# POWER.net
KiCad netlist of a schematic drawn in Altium Designer
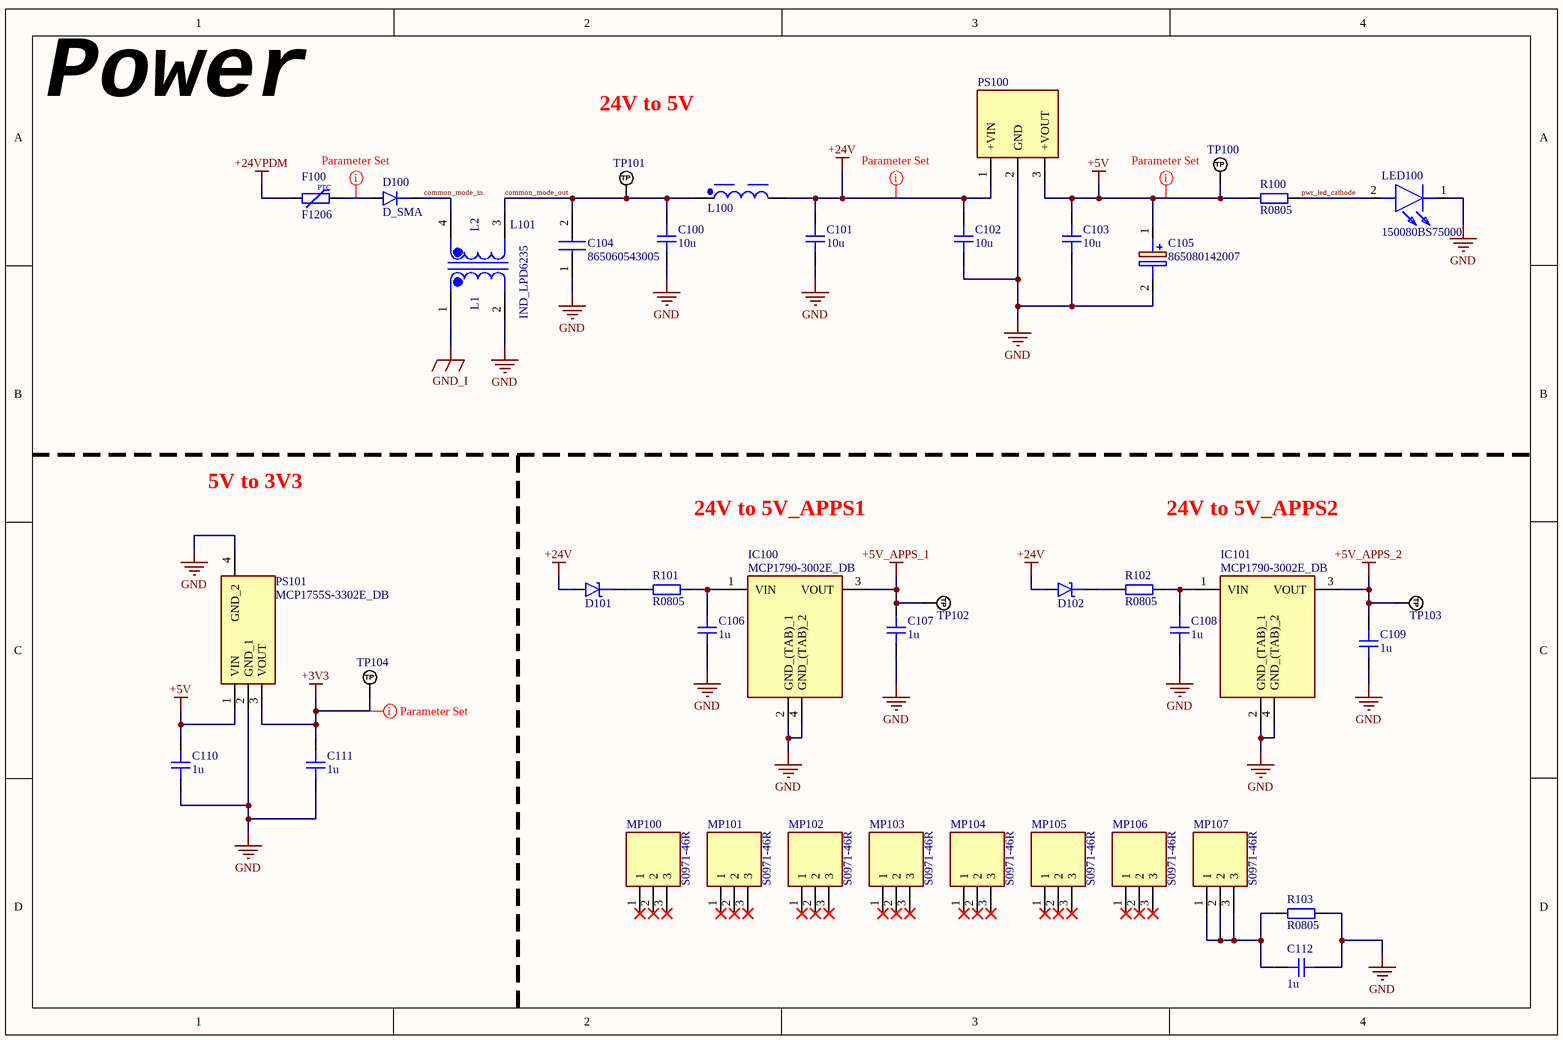
[diagram p0: POWER.SchDoc]

(export (version "E")
  (design (tool "Eeschema 10.0.6"))
  (components
    (comp (ref "C100")
      (value "10u")
      (footprint "CAP_0805")
      (description "Capacitor SMD 0805 10V")
      (libsource (lib "Schematic-Lib-PhilsLab") (part "CAP_0805_10V"))
    )
    (comp (ref "C101")
      (value "10u")
      (footprint "CAP_0805")
      (description "Capacitor SMD 0805 10V")
      (libsource (lib "Schematic-Lib-PhilsLab") (part "CAP_0805_10V"))
    )
    (comp (ref "C102")
      (value "10u")
      (footprint "CAP_0805")
      (description "Capacitor SMD 0805 10V")
      (libsource (lib "Schematic-Lib-PhilsLab") (part "CAP_0805_10V"))
    )
    (comp (ref "C103")
      (value "10u")
      (footprint "CAP_0805")
      (description "Capacitor SMD 0805 10V")
      (libsource (lib "Schematic-Lib-PhilsLab") (part "CAP_0805_10V"))
    )
    (comp (ref "C104")
      (value "865060543005")
      (footprint "Pedro_pcb_lib:865060543005")
      (description "Capacitor")
      (fields (field (name "MOUSER PART NUMBER") "710-865060543005"))
      (libsource (lib "*") (part "865060543005"))
    )
    (comp (ref "C105")
      (value "865080142007")
      (footprint "Pedro_pcb_lib:CAPAE530X550N")
      (description "Capacitor Polarised")
      (fields (field (name "MOUSER PART NUMBER") "710-865080142007"))
      (libsource (lib "*") (part "865080142007"))
    )
    (comp (ref "C106")
      (value "1u")
      (footprint "CAP_0805")
      (description "Capacitor SMD 0805 10V")
      (libsource (lib "Schematic-Lib-PhilsLab") (part "CAP_0805_10V"))
    )
    (comp (ref "C107")
      (value "1u")
      (footprint "CAP_0805")
      (description "Capacitor SMD 0805 10V")
      (libsource (lib "Schematic-Lib-PhilsLab") (part "CAP_0805_10V"))
    )
    (comp (ref "C108")
      (value "1u")
      (footprint "CAP_0805")
      (description "Capacitor SMD 0805 10V")
      (libsource (lib "Schematic-Lib-PhilsLab") (part "CAP_0805_10V"))
    )
    (comp (ref "C109")
      (value "1u")
      (footprint "CAP_0805")
      (description "Capacitor SMD 0805 10V")
      (libsource (lib "Schematic-Lib-PhilsLab") (part "CAP_0805_10V"))
    )
    (comp (ref "C110")
      (value "1u")
      (footprint "CAP_0805")
      (description "Capacitor SMD 0805 10V")
      (libsource (lib "Schematic-Lib-PhilsLab") (part "CAP_0805_10V"))
    )
    (comp (ref "C111")
      (value "1u")
      (footprint "CAP_0805")
      (description "Capacitor SMD 0805 10V")
      (libsource (lib "Schematic-Lib-PhilsLab") (part "CAP_0805_10V"))
    )
    (comp (ref "C112")
      (value "1u")
      (footprint "CAP_0805")
      (description "Capacitor SMD 0805 10V")
      (libsource (lib "Schematic-Lib-PhilsLab") (part "CAP_0805_10V"))
    )
    (comp (ref "D100")
      (value "D_SMA")
      (footprint "DO-214AC-2 (SMA)")
      (description "Diode SMD SMA (DO-214AA)")
      (libsource (lib "Schematic-Lib-PhilsLab") (part "D_SMA"))
    )
    (comp (ref "D101")
      (value "D_SCHOTTKY_SOD_323")
      (footprint "SOD-323")
      (description "Diode Schottky SMD SOD-323")
      (libsource (lib "PhilsLab") (part "D_SCHOTTKY_SOD_323"))
    )
    (comp (ref "D102")
      (value "D_SCHOTTKY_SOD_323")
      (footprint "SOD-323")
      (description "Diode Schottky SMD SOD-323")
      (libsource (lib "PhilsLab") (part "D_SCHOTTKY_SOD_323"))
    )
    (comp (ref "F100")
      (value "F1206")
      (footprint "FUSE_1206")
      (description "Fuse PPTC SMD 1206")
      (libsource (lib "Schematic-Lib-PhilsLab") (part "FUSE_PPTC_1206"))
    )
    (comp (ref "IC100")
      (value "MCP1790-3002E_DB")
      (footprint "Pedro_pcb_lib:SOT230P700X180-4N")
      (description "Integrated Circuit")
      (fields
        (field (name "MANUFACTURER_PART_NUMBER") "MCP1790-3002E/DB")
        (field (name "MOUSER PART NUMBER") "579-MCP1790-3002E/DB")
      )
      (libsource (lib "*") (part "MCP1790-3002E_DB"))
    )
    (comp (ref "IC101")
      (value "MCP1790-3002E_DB")
      (footprint "Pedro_pcb_lib:SOT230P700X180-4N")
      (description "Integrated Circuit")
      (fields
        (field (name "MANUFACTURER_PART_NUMBER") "MCP1790-3002E/DB")
        (field (name "MOUSER PART NUMBER") "579-MCP1790-3002E/DB")
      )
      (libsource (lib "*") (part "MCP1790-3002E_DB"))
    )
    (comp (ref "L100")
      (value "5.6uH, 8.7A")
      (footprint "WE-PD_1280")
      (description "WE-PD SMT Power Inductor, size 1280, 5.6uH, 8.7A, 13.5mOhm")
      (fields
        (field (name "MANUFACTURER PART NUMBER") "74477005")
        (field (name "MANUFACTURER") "Wurth Elektronik")
      )
      (libsource (lib "WE-PD (rev22g)") (part "74477005"))
    )
    (comp (ref "L101")
      (value "IND_LPD6235")
      (footprint "IND_LPD6235")
      (libsource (lib "Pedro_Integrated_Library") (part "IND_LPD6235"))
    )
    (comp (ref "LED100")
      (value "150080BS75000")
      (footprint "LEDC2012X80N")
      (description "LED")
      (fields (field (name "MOUSER PART NUMBER") "710-150080BS75000"))
      (libsource (lib "Pedro_Integrated_Library") (part "150080BS75000"))
    )
    (comp (ref "MP100")
      (value "S0971-46R")
      (footprint "Pedro_pcb_lib:S097146R")
      (description "Mechanical Part")
      (fields (field (name "MOUSER PART NUMBER") "855-S0971-46R"))
      (libsource (lib "*") (part "S0971-46R"))
    )
    (comp (ref "MP101")
      (value "S0971-46R")
      (footprint "Pedro_pcb_lib:S097146R")
      (description "Mechanical Part")
      (fields (field (name "MOUSER PART NUMBER") "855-S0971-46R"))
      (libsource (lib "*") (part "S0971-46R"))
    )
    (comp (ref "MP102")
      (value "S0971-46R")
      (footprint "Pedro_pcb_lib:S097146R")
      (description "Mechanical Part")
      (fields (field (name "MOUSER PART NUMBER") "855-S0971-46R"))
      (libsource (lib "*") (part "S0971-46R"))
    )
    (comp (ref "MP103")
      (value "S0971-46R")
      (footprint "Pedro_pcb_lib:S097146R")
      (description "Mechanical Part")
      (fields (field (name "MOUSER PART NUMBER") "855-S0971-46R"))
      (libsource (lib "*") (part "S0971-46R"))
    )
    (comp (ref "MP104")
      (value "S0971-46R")
      (footprint "Pedro_pcb_lib:S097146R")
      (description "Mechanical Part")
      (fields (field (name "MOUSER PART NUMBER") "855-S0971-46R"))
      (libsource (lib "*") (part "S0971-46R"))
    )
    (comp (ref "MP105")
      (value "S0971-46R")
      (footprint "Pedro_pcb_lib:S097146R")
      (description "Mechanical Part")
      (fields (field (name "MOUSER PART NUMBER") "855-S0971-46R"))
      (libsource (lib "*") (part "S0971-46R"))
    )
    (comp (ref "MP106")
      (value "S0971-46R")
      (footprint "Pedro_pcb_lib:S097146R")
      (description "Mechanical Part")
      (fields (field (name "MOUSER PART NUMBER") "855-S0971-46R"))
      (libsource (lib "*") (part "S0971-46R"))
    )
    (comp (ref "MP107")
      (value "S0971-46R")
      (footprint "Pedro_pcb_lib:S097146R")
      (description "Mechanical Part")
      (fields (field (name "MOUSER PART NUMBER") "855-S0971-46R"))
      (libsource (lib "*") (part "S0971-46R"))
    )
    (comp (ref "PS100")
      (value "R-78E5.0-0.5")
      (footprint "R78E5005")
      (description "Power Supply")
      (fields (field (name "MOUSER PART NUMBER") "919-R-78E5.0-0.5"))
      (libsource (lib "Pedro_Integrated_Library") (part "R-78E5.0-0.5"))
    )
    (comp (ref "PS101")
      (value "MCP1755S-3302E_DB")
      (footprint "Pedro_pcb_lib:SOT230P700X180-4N")
      (description "Power Supply")
      (fields
        (field (name "MANUFACTURER_PART_NUMBER") "MCP1755S-3302E/DB")
        (field (name "MOUSER PART NUMBER") "579-MCP1755S-3302EDB")
      )
      (libsource (lib "*") (part "MCP1755S-3302E_DB"))
    )
    (comp (ref "R100")
      (value "R0805")
      (footprint "RES_0805")
      (description "Resistor SMD 0805")
      (libsource (lib "Schematic-Lib-PhilsLab") (part "RES_0805"))
    )
    (comp (ref "R101")
      (value "R0805")
      (footprint "RES_0805")
      (description "Resistor SMD 0805")
      (libsource (lib "Schematic-Lib-PhilsLab") (part "RES_0805"))
    )
    (comp (ref "R102")
      (value "R0805")
      (footprint "RES_0805")
      (description "Resistor SMD 0805")
      (libsource (lib "Schematic-Lib-PhilsLab") (part "RES_0805"))
    )
    (comp (ref "R103")
      (value "R0805")
      (footprint "RES_0805")
      (description "Resistor SMD 0805")
      (libsource (lib "Schematic-Lib-PhilsLab") (part "RES_0805"))
    )
    (comp (ref "TP100")
      (value "TP_NOBOM")
      (footprint "PAD_RND_1MM")
      (description "Test Point Round 1mm (NO BOM)")
      (libsource (lib "Schematic-Lib-PhilsLab") (part "TEST_POINT_RND_1MM"))
    )
    (comp (ref "TP101")
      (value "TP_NOBOM")
      (footprint "PAD_RND_1MM")
      (description "Test Point Round 1mm (NO BOM)")
      (libsource (lib "Schematic-Lib-PhilsLab") (part "TEST_POINT_RND_1MM"))
    )
    (comp (ref "TP102")
      (value "TP_NOBOM")
      (footprint "PAD_RND_1MM")
      (description "Test Point Round 1mm (NO BOM)")
      (libsource (lib "Schematic-Lib-PhilsLab") (part "TEST_POINT_RND_1MM"))
    )
    (comp (ref "TP103")
      (value "TP_NOBOM")
      (footprint "PAD_RND_1MM")
      (description "Test Point Round 1mm (NO BOM)")
      (libsource (lib "Schematic-Lib-PhilsLab") (part "TEST_POINT_RND_1MM"))
    )
    (comp (ref "TP104")
      (value "TP_NOBOM")
      (footprint "PAD_RND_1MM")
      (description "Test Point Round 1mm (NO BOM)")
      (libsource (lib "Schematic-Lib-PhilsLab") (part "TEST_POINT_RND_1MM"))
    )
  )
  (nets
    (net (code "1") (name "+3V3") (class "Default")
      (node (ref "C111") (pin "1") (pinfunction "1_1") (pintype "passive"))
      (node (ref "PS101") (pin "3") (pinfunction "VOUT_3") (pintype "passive"))
      (node (ref "TP104") (pin "1") (pinfunction "TP_1") (pintype "passive"))
    )
    (net (code "2") (name "+5V") (class "Default")
      (node (ref "C103") (pin "2") (pinfunction "2_2") (pintype "passive"))
      (node (ref "C105") (pin "1") (pinfunction "+_1") (pintype "passive"))
      (node (ref "C110") (pin "1") (pinfunction "1_1") (pintype "passive"))
      (node (ref "PS100") (pin "3") (pinfunction "+VOUT_3") (pintype "passive"))
      (node (ref "PS101") (pin "1") (pinfunction "VIN_1") (pintype "passive"))
      (node (ref "R100") (pin "1") (pinfunction "1_1") (pintype "passive"))
      (node (ref "TP100") (pin "1") (pinfunction "TP_1") (pintype "passive"))
    )
    (net (code "3") (name "+5V_APPS_1") (class "Default")
      (node (ref "C107") (pin "1") (pinfunction "1_1") (pintype "passive"))
      (node (ref "IC100") (pin "3") (pinfunction "VOUT_3") (pintype "passive"))
      (node (ref "TP102") (pin "1") (pinfunction "TP_1") (pintype "passive"))
    )
    (net (code "4") (name "+5V_APPS_2") (class "Default")
      (node (ref "C109") (pin "1") (pinfunction "1_1") (pintype "passive"))
      (node (ref "IC101") (pin "3") (pinfunction "VOUT_3") (pintype "passive"))
      (node (ref "TP103") (pin "1") (pinfunction "TP_1") (pintype "passive"))
    )
    (net (code "5") (name "+24V") (class "Default")
      (node (ref "C101") (pin "2") (pinfunction "2_2") (pintype "passive"))
      (node (ref "C102") (pin "2") (pinfunction "2_2") (pintype "passive"))
      (node (ref "D101") (pin "A") (pinfunction "A_A") (pintype "passive"))
      (node (ref "D102") (pin "A") (pinfunction "A_A") (pintype "passive"))
      (node (ref "L100") (pin "2") (pinfunction "2_2") (pintype "passive"))
      (node (ref "PS100") (pin "1") (pinfunction "+VIN_1") (pintype "passive"))
    )
    (net (code "6") (name "+24VPDM") (class "Default")
      (node (ref "F100") (pin "1") (pinfunction "1_1") (pintype "passive"))
    )
    (net (code "7") (name "/common_mode_in") (class "Default")
      (node (ref "D100") (pin "K") (pinfunction "K_K") (pintype "passive"))
      (node (ref "L101") (pin "4") (pinfunction "4_4") (pintype "passive"))
    )
    (net (code "8") (name "/common_mode_out") (class "Default")
      (node (ref "C100") (pin "2") (pinfunction "2_2") (pintype "passive"))
      (node (ref "C104") (pin "2") (pinfunction "-_2") (pintype "passive"))
      (node (ref "L100") (pin "1") (pinfunction "1_1") (pintype "passive"))
      (node (ref "L101") (pin "3") (pinfunction "3_3") (pintype "passive"))
      (node (ref "TP101") (pin "1") (pinfunction "TP_1") (pintype "passive"))
    )
    (net (code "9") (name "/pwr_led_cathode") (class "Default")
      (node (ref "LED100") (pin "2") (pinfunction "A_2") (pintype "passive"))
      (node (ref "R100") (pin "2") (pinfunction "2_2") (pintype "passive"))
    )
    (net (code "10") (name "GND") (class "Default")
      (node (ref "C100") (pin "1") (pinfunction "1_1") (pintype "passive"))
      (node (ref "C101") (pin "1") (pinfunction "1_1") (pintype "passive"))
      (node (ref "C102") (pin "1") (pinfunction "1_1") (pintype "passive"))
      (node (ref "C103") (pin "1") (pinfunction "1_1") (pintype "passive"))
      (node (ref "C104") (pin "1") (pinfunction "+_1") (pintype "passive"))
      (node (ref "C105") (pin "2") (pinfunction "-_2") (pintype "passive"))
      (node (ref "C106") (pin "2") (pinfunction "2_2") (pintype "passive"))
      (node (ref "C107") (pin "2") (pinfunction "2_2") (pintype "passive"))
      (node (ref "C108") (pin "2") (pinfunction "2_2") (pintype "passive"))
      (node (ref "C109") (pin "2") (pinfunction "2_2") (pintype "passive"))
      (node (ref "C110") (pin "2") (pinfunction "2_2") (pintype "passive"))
      (node (ref "C111") (pin "2") (pinfunction "2_2") (pintype "passive"))
      (node (ref "C112") (pin "2") (pinfunction "2_2") (pintype "passive"))
      (node (ref "IC100") (pin "2") (pinfunction "GND_(TAB)_1_2") (pintype "passive"))
      (node (ref "IC100") (pin "4") (pinfunction "GND_(TAB)_2_4") (pintype "passive"))
      (node (ref "IC101") (pin "2") (pinfunction "GND_(TAB)_1_2") (pintype "passive"))
      (node (ref "IC101") (pin "4") (pinfunction "GND_(TAB)_2_4") (pintype "passive"))
      (node (ref "L101") (pin "2") (pinfunction "2_2") (pintype "passive"))
      (node (ref "LED100") (pin "1") (pinfunction "K_1") (pintype "passive"))
      (node (ref "PS100") (pin "2") (pinfunction "GND_2") (pintype "passive"))
      (node (ref "PS101") (pin "2") (pinfunction "GND_1_2") (pintype "passive"))
      (node (ref "PS101") (pin "4") (pinfunction "GND_2_4") (pintype "passive"))
      (node (ref "R103") (pin "1") (pinfunction "1_1") (pintype "passive"))
    )
    (net (code "11") (name "GND_I") (class "Default")
      (node (ref "L101") (pin "1") (pinfunction "1_1") (pintype "passive"))
    )
    (net (code "12") (name "Net-(C112-Pad1)") (class "Default")
      (node (ref "C112") (pin "1") (pinfunction "1_1") (pintype "passive"))
      (node (ref "MP107") (pin "1") (pinfunction "1_1") (pintype "passive"))
      (node (ref "MP107") (pin "2") (pinfunction "2_2") (pintype "passive"))
      (node (ref "MP107") (pin "3") (pinfunction "3_3") (pintype "passive"))
      (node (ref "R103") (pin "2") (pinfunction "2_2") (pintype "passive"))
    )
    (net (code "13") (name "Net-(D100-PadA)") (class "Default")
      (node (ref "D100") (pin "A") (pinfunction "A_A") (pintype "passive"))
      (node (ref "F100") (pin "2") (pinfunction "2_2") (pintype "passive"))
    )
    (net (code "14") (name "Net-(D101-PadK)") (class "Default")
      (node (ref "D101") (pin "K") (pinfunction "K_K") (pintype "passive"))
      (node (ref "R101") (pin "2") (pinfunction "2_2") (pintype "passive"))
    )
    (net (code "15") (name "Net-(D102-PadK)") (class "Default")
      (node (ref "D102") (pin "K") (pinfunction "K_K") (pintype "passive"))
      (node (ref "R102") (pin "2") (pinfunction "2_2") (pintype "passive"))
    )
    (net (code "16") (name "Net-(IC100-VIN)") (class "Default")
      (node (ref "C106") (pin "1") (pinfunction "1_1") (pintype "passive"))
      (node (ref "IC100") (pin "1") (pinfunction "VIN_1") (pintype "passive"))
      (node (ref "R101") (pin "1") (pinfunction "1_1") (pintype "passive"))
    )
    (net (code "17") (name "Net-(IC101-VIN)") (class "Default")
      (node (ref "C108") (pin "1") (pinfunction "1_1") (pintype "passive"))
      (node (ref "IC101") (pin "1") (pinfunction "VIN_1") (pintype "passive"))
      (node (ref "R102") (pin "1") (pinfunction "1_1") (pintype "passive"))
    )
    (net (code "18") (name "unconnected-(MP100-Pad1)") (class "Default")
      (node (ref "MP100") (pin "1") (pinfunction "1_1") (pintype "passive+no_connect"))
    )
    (net (code "19") (name "unconnected-(MP100-Pad2)") (class "Default")
      (node (ref "MP100") (pin "2") (pinfunction "2_2") (pintype "passive+no_connect"))
    )
    (net (code "20") (name "unconnected-(MP100-Pad3)") (class "Default")
      (node (ref "MP100") (pin "3") (pinfunction "3_3") (pintype "passive+no_connect"))
    )
    (net (code "21") (name "unconnected-(MP101-Pad1)") (class "Default")
      (node (ref "MP101") (pin "1") (pinfunction "1_1") (pintype "passive+no_connect"))
    )
    (net (code "22") (name "unconnected-(MP101-Pad2)") (class "Default")
      (node (ref "MP101") (pin "2") (pinfunction "2_2") (pintype "passive+no_connect"))
    )
    (net (code "23") (name "unconnected-(MP101-Pad3)") (class "Default")
      (node (ref "MP101") (pin "3") (pinfunction "3_3") (pintype "passive+no_connect"))
    )
    (net (code "24") (name "unconnected-(MP102-Pad1)") (class "Default")
      (node (ref "MP102") (pin "1") (pinfunction "1_1") (pintype "passive+no_connect"))
    )
    (net (code "25") (name "unconnected-(MP102-Pad2)") (class "Default")
      (node (ref "MP102") (pin "2") (pinfunction "2_2") (pintype "passive+no_connect"))
    )
    (net (code "26") (name "unconnected-(MP102-Pad3)") (class "Default")
      (node (ref "MP102") (pin "3") (pinfunction "3_3") (pintype "passive+no_connect"))
    )
    (net (code "27") (name "unconnected-(MP103-Pad1)") (class "Default")
      (node (ref "MP103") (pin "1") (pinfunction "1_1") (pintype "passive+no_connect"))
    )
    (net (code "28") (name "unconnected-(MP103-Pad2)") (class "Default")
      (node (ref "MP103") (pin "2") (pinfunction "2_2") (pintype "passive+no_connect"))
    )
    (net (code "29") (name "unconnected-(MP103-Pad3)") (class "Default")
      (node (ref "MP103") (pin "3") (pinfunction "3_3") (pintype "passive+no_connect"))
    )
    (net (code "30") (name "unconnected-(MP104-Pad1)") (class "Default")
      (node (ref "MP104") (pin "1") (pinfunction "1_1") (pintype "passive+no_connect"))
    )
    (net (code "31") (name "unconnected-(MP104-Pad2)") (class "Default")
      (node (ref "MP104") (pin "2") (pinfunction "2_2") (pintype "passive+no_connect"))
    )
    (net (code "32") (name "unconnected-(MP104-Pad3)") (class "Default")
      (node (ref "MP104") (pin "3") (pinfunction "3_3") (pintype "passive+no_connect"))
    )
    (net (code "33") (name "unconnected-(MP105-Pad1)") (class "Default")
      (node (ref "MP105") (pin "1") (pinfunction "1_1") (pintype "passive+no_connect"))
    )
    (net (code "34") (name "unconnected-(MP105-Pad2)") (class "Default")
      (node (ref "MP105") (pin "2") (pinfunction "2_2") (pintype "passive+no_connect"))
    )
    (net (code "35") (name "unconnected-(MP105-Pad3)") (class "Default")
      (node (ref "MP105") (pin "3") (pinfunction "3_3") (pintype "passive+no_connect"))
    )
    (net (code "36") (name "unconnected-(MP106-Pad1)") (class "Default")
      (node (ref "MP106") (pin "1") (pinfunction "1_1") (pintype "passive+no_connect"))
    )
    (net (code "37") (name "unconnected-(MP106-Pad2)") (class "Default")
      (node (ref "MP106") (pin "2") (pinfunction "2_2") (pintype "passive+no_connect"))
    )
    (net (code "38") (name "unconnected-(MP106-Pad3)") (class "Default")
      (node (ref "MP106") (pin "3") (pinfunction "3_3") (pintype "passive+no_connect"))
    )
  )
)
